# External_Power_schematic.net
KiCad netlist of a schematic drawn in Altium Designer
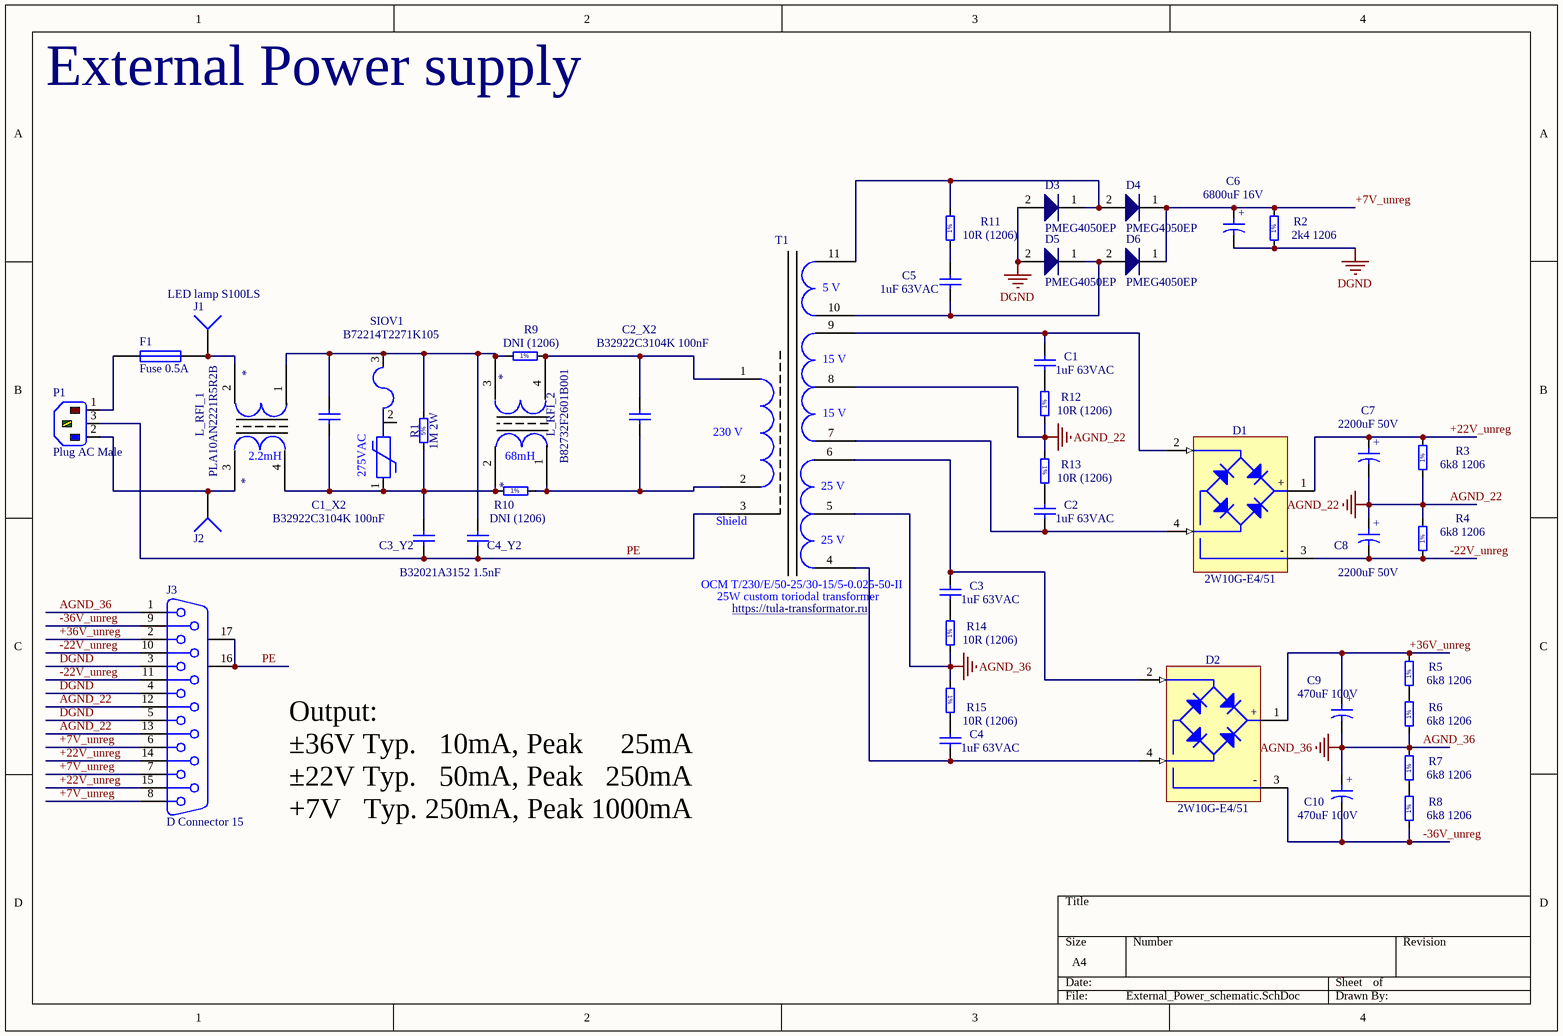
[diagram p0: External_Power_schematic.SchDoc]

(export (version "E")
  (design (tool "Eeschema 10.0.6"))
  (components
    (comp (ref "C1")
      (value "1uF 63VAC")
      (footprint "B32522C1105")
      (description "Non-polarised capacitor")
      (fields
        (field (name "PART NUMBER") "CPPR_330NF_630V_5%_2250-1050X2650X1650")
        (field (name "VOLTAGE") "630VDC/250VAC")
        (field (name "AUTHOR") "CERN DEM JLC")
      )
      (libsource (lib "Capacitors") (part "Capacitor - non polarized"))
    )
    (comp (ref "C1_X2")
      (value "B32922C3104K 100nF")
      (footprint "B32922D3334K")
      (description "Non-polarised capacitor")
      (fields
        (field (name "PART NUMBER") "CPPR_330NF_630V_5%_2250-1050X2650X1650")
        (field (name "VOLTAGE") "630VDC/250VAC")
        (field (name "AUTHOR") "CERN DEM JLC")
      )
      (libsource (lib "Capacitors") (part "Capacitor - non polarized"))
    )
    (comp (ref "C2")
      (value "1uF 63VAC")
      (footprint "B32522C1105")
      (description "Non-polarised capacitor")
      (fields
        (field (name "PART NUMBER") "CPPR_330NF_630V_5%_2250-1050X2650X1650")
        (field (name "VOLTAGE") "630VDC/250VAC")
        (field (name "AUTHOR") "CERN DEM JLC")
      )
      (libsource (lib "Capacitors") (part "Capacitor - non polarized"))
    )
    (comp (ref "C2_X2")
      (value "B32922C3104K 100nF")
      (footprint "B32922D3334K")
      (description "Non-polarised capacitor")
      (fields
        (field (name "PART NUMBER") "CPPR_330NF_630V_5%_2250-1050X2650X1650")
        (field (name "VOLTAGE") "630VDC/250VAC")
        (field (name "AUTHOR") "CERN DEM JLC")
      )
      (libsource (lib "Capacitors") (part "Capacitor - non polarized"))
    )
    (comp (ref "C3")
      (value "1uF 63VAC")
      (footprint "B32522C1105")
      (description "Non-polarised capacitor")
      (fields
        (field (name "PART NUMBER") "CPPR_330NF_630V_5%_2250-1050X2650X1650")
        (field (name "VOLTAGE") "630VDC/250VAC")
        (field (name "AUTHOR") "CERN DEM JLC")
      )
      (libsource (lib "Capacitors") (part "Capacitor - non polarized"))
    )
    (comp (ref "C3_Y2")
      (value "B32021A3152 1.5nF")
      (footprint "B32021A3152")
      (description "Non-polarised capacitor")
      (fields
        (field (name "PART NUMBER") "CPPR_330NF_630V_5%_2250-1050X2650X1650")
        (field (name "VOLTAGE") "630VDC/250VAC")
        (field (name "AUTHOR") "CERN DEM JLC")
      )
      (libsource (lib "Capacitors") (part "Capacitor - non polarized"))
    )
    (comp (ref "C4")
      (value "1uF 63VAC")
      (footprint "B32522C1105")
      (description "Non-polarised capacitor")
      (fields
        (field (name "PART NUMBER") "CPPR_330NF_630V_5%_2250-1050X2650X1650")
        (field (name "VOLTAGE") "630VDC/250VAC")
        (field (name "AUTHOR") "CERN DEM JLC")
      )
      (libsource (lib "Capacitors") (part "Capacitor - non polarized"))
    )
    (comp (ref "C4_Y2")
      (value "B32021A3152 1.5nF")
      (footprint "B32021A3152")
      (description "Non-polarised capacitor")
      (fields
        (field (name "PART NUMBER") "CPPR_330NF_630V_5%_2250-1050X2650X1650")
        (field (name "VOLTAGE") "630VDC/250VAC")
        (field (name "AUTHOR") "CERN DEM JLC")
      )
      (libsource (lib "Capacitors") (part "Capacitor - non polarized"))
    )
    (comp (ref "C5")
      (value "1uF 63VAC")
      (footprint "B32522C1475")
      (description "Non-polarised capacitor")
      (fields
        (field (name "PART NUMBER") "CPPR_330NF_630V_5%_2250-1050X2650X1650")
        (field (name "VOLTAGE") "630VDC/250VAC")
        (field (name "AUTHOR") "CERN DEM JLC")
      )
      (libsource (lib "Capacitors") (part "Capacitor - non polarized"))
    )
    (comp (ref "C6")
      (value "6800uF 16V")
      (footprint "CAPPR750-1850X3750")
      (description "Polarised capacitor")
      (fields
        (field (name "PART NUMBER") "CAER_10000UF_16V_20%_CHEMI-CON_EKYB160ELL103MMP1S")
        (field (name "VOLTAGE") "16V")
        (field (name "AUTHOR") "CERN DEM JLC")
      )
      (libsource (lib "Capacitors") (part "Capacitor - polarized"))
    )
    (comp (ref "C7")
      (value "2200uF 50V")
      (footprint "CAPPR750-1850X3750")
      (description "Polarised capacitor")
      (fields
        (field (name "PART NUMBER") "CAER_10000UF_16V_20%_CHEMI-CON_EKYB160ELL103MMP1S")
        (field (name "VOLTAGE") "16V")
        (field (name "AUTHOR") "CERN DEM JLC")
      )
      (libsource (lib "Capacitors") (part "Capacitor - polarized"))
    )
    (comp (ref "C8")
      (value "2200uF 50V")
      (footprint "CAPPR750-1850X3750")
      (description "Polarised capacitor")
      (fields
        (field (name "PART NUMBER") "CAER_10000UF_16V_20%_CHEMI-CON_EKYB160ELL103MMP1S")
        (field (name "VOLTAGE") "16V")
        (field (name "AUTHOR") "CERN DEM JLC")
      )
      (libsource (lib "Capacitors") (part "Capacitor - polarized"))
    )
    (comp (ref "C9")
      (value "470uF 100V")
      (footprint "CAPPR750-1850X3750")
      (description "Polarised capacitor")
      (fields
        (field (name "PART NUMBER") "CAER_10000UF_16V_20%_CHEMI-CON_EKYB160ELL103MMP1S")
        (field (name "VOLTAGE") "16V")
        (field (name "AUTHOR") "CERN DEM JLC")
      )
      (libsource (lib "Capacitors") (part "Capacitor - polarized"))
    )
    (comp (ref "C10")
      (value "470uF 100V")
      (footprint "CAPPR750-1850X3750")
      (description "Polarised capacitor")
      (fields
        (field (name "PART NUMBER") "CAER_10000UF_16V_20%_CHEMI-CON_EKYB160ELL103MMP1S")
        (field (name "VOLTAGE") "16V")
        (field (name "AUTHOR") "CERN DEM JLC")
      )
      (libsource (lib "Capacitors") (part "Capacitor - polarized"))
    )
    (comp (ref "D1")
      (value "2W10G-E4/51")
      (footprint "VISHAY_WOG")
      (description "Bridge Rectifier 1+ 2AC 3- 4AC")
      (fields
        (field (name "PART NUMBER") "W005G-E4/51")
        (field (name "VOLTAGE") "50V")
        (field (name "AUTHOR") "CERN DEM JLC")
      )
      (libsource (lib "ICs And Semiconductors") (part "Bridge Rectifier 1+ 2AC 3- 4AC"))
    )
    (comp (ref "D2")
      (value "2W10G-E4/51")
      (footprint "VISHAY_WOG")
      (description "Bridge Rectifier 1+ 2AC 3- 4AC")
      (fields
        (field (name "PART NUMBER") "W005G-E4/51")
        (field (name "VOLTAGE") "50V")
        (field (name "AUTHOR") "CERN DEM JLC")
      )
      (libsource (lib "ICs And Semiconductors") (part "Bridge Rectifier 1+ 2AC 3- 4AC"))
    )
    (comp (ref "D3")
      (value "PMEG4050EP")
      (footprint "PMEG4050EP")
      (libsource (lib "My SCH library") (part "PMEG4050EP"))
    )
    (comp (ref "D4")
      (value "PMEG4050EP")
      (footprint "PMEG4050EP")
      (libsource (lib "My SCH library") (part "PMEG4050EP"))
    )
    (comp (ref "D5")
      (value "PMEG4050EP")
      (footprint "PMEG4050EP")
      (libsource (lib "My SCH library") (part "PMEG4050EP"))
    )
    (comp (ref "D6")
      (value "PMEG4050EP")
      (footprint "PMEG4050EP")
      (libsource (lib "My SCH library") (part "PMEG4050EP"))
    )
    (comp (ref "F1")
      (value "Fuse 0.5A")
      (footprint "FUSE")
      (description "Fuse")
      (fields (field (name "PUBLISHER") "Altium Limited"))
      (libsource (lib "Miscellaneous Devices") (part "Fuse 1"))
    )
    (comp (ref "J1")
      (value "Socket")
      (footprint "PIN1")
      (fields (field (name "PUBLISHER") "Altium Limited"))
      (libsource (lib "Miscellaneous Connectors") (part "Socket"))
    )
    (comp (ref "J2")
      (value "Socket")
      (footprint "PIN1")
      (fields (field (name "PUBLISHER") "Altium Limited"))
      (libsource (lib "Miscellaneous Connectors") (part "Socket"))
    )
    (comp (ref "J3")
      (value "D Connector 15")
      (footprint "DSUB1.385-2H15")
      (description "Receptacle Assembly, 15 Position, Right Angle")
      (fields (field (name "PUBLISHER") "Altium Limited"))
      (libsource (lib "Miscellaneous Connectors") (part "D Connector 15"))
    )
    (comp (ref "L_RFI_1")
      (value "PLA10AN2221R5R2B")
      (footprint "PLA10AN2221R5R2B")
      (libsource (lib "") (part "PLA10AN2221R5R2B_1"))
    )
    (comp (ref "L_RFI_2")
      (value "B82732F2601B001")
      (footprint "B82732F")
      (libsource (lib "My SCH library") (part "PLA10AN2221R5R2B"))
    )
    (comp (ref "P1")
      (value "Plug AC Male")
      (footprint "AS-205")
      (description "IEC Mains Power Inlet, EN60 320-1 C14 Class I Cold Condition, PC Flange Rear Mount, Chassis Plug")
      (fields (field (name "PUBLISHER") "Altium Limited"))
      (libsource (lib "Miscellaneous Connectors") (part "Plug AC Male"))
    )
    (comp (ref "R1")
      (value "1M 2W")
      (footprint "RES_TYCO_CFR200")
      (description "Resistor - 5%")
      (fields
        (field (name "PART NUMBER") "RCF_NO-VALUE_5%_2W_0-450PPM_TYCO_CFR200")
        (field (name "POWER") "2W")
        (field (name "AUTHOR") "CERN DEM JLC")
      )
      (libsource (lib "Resistors") (part "Resistor - 5%"))
    )
    (comp (ref "R2")
      (value "2k4 1206")
      (footprint "RESC3216X65N")
      (description "Resistor - 1%")
      (fields
        (field (name "PART NUMBER") "R1206_2K4_1%_0.25W_100PPM")
        (field (name "POWER") "0.25W")
        (field (name "AUTHOR") "CERN DEM JLC")
      )
      (libsource (lib "Resistors") (part "Resistor - 1%"))
    )
    (comp (ref "R3")
      (value "6k8 1206")
      (footprint "RESC3216X65N")
      (description "Resistor - 1%")
      (fields
        (field (name "PART NUMBER") "R1206_2K4_1%_0.25W_100PPM")
        (field (name "POWER") "0.25W")
        (field (name "AUTHOR") "CERN DEM JLC")
      )
      (libsource (lib "Resistors") (part "Resistor - 1%"))
    )
    (comp (ref "R4")
      (value "6k8 1206")
      (footprint "RESC3216X65N")
      (description "Resistor - 1%")
      (fields
        (field (name "PART NUMBER") "R1206_2K4_1%_0.25W_100PPM")
        (field (name "POWER") "0.25W")
        (field (name "AUTHOR") "CERN DEM JLC")
      )
      (libsource (lib "Resistors") (part "Resistor - 1%"))
    )
    (comp (ref "R5")
      (value "6k8 1206")
      (footprint "RESC3216X65N")
      (description "Resistor - 1%")
      (fields
        (field (name "PART NUMBER") "R1206_2K4_1%_0.25W_100PPM")
        (field (name "POWER") "0.25W")
        (field (name "AUTHOR") "CERN DEM JLC")
      )
      (libsource (lib "Resistors") (part "Resistor - 1%"))
    )
    (comp (ref "R6")
      (value "6k8 1206")
      (footprint "RESC3216X65N")
      (description "Resistor - 1%")
      (fields
        (field (name "PART NUMBER") "R1206_2K4_1%_0.25W_100PPM")
        (field (name "POWER") "0.25W")
        (field (name "AUTHOR") "CERN DEM JLC")
      )
      (libsource (lib "Resistors") (part "Resistor - 1%"))
    )
    (comp (ref "R7")
      (value "6k8 1206")
      (footprint "RESC3216X65N")
      (description "Resistor - 1%")
      (fields
        (field (name "PART NUMBER") "R1206_2K4_1%_0.25W_100PPM")
        (field (name "POWER") "0.25W")
        (field (name "AUTHOR") "CERN DEM JLC")
      )
      (libsource (lib "Resistors") (part "Resistor - 1%"))
    )
    (comp (ref "R8")
      (value "6k8 1206")
      (footprint "RESC3216X65N")
      (description "Resistor - 1%")
      (fields
        (field (name "PART NUMBER") "R1206_2K4_1%_0.25W_100PPM")
        (field (name "POWER") "0.25W")
        (field (name "AUTHOR") "CERN DEM JLC")
      )
      (libsource (lib "Resistors") (part "Resistor - 1%"))
    )
    (comp (ref "R9")
      (value "DNI (1206)")
      (footprint "RESC3216X65N")
      (description "Resistor - 1%")
      (fields
        (field (name "PART NUMBER") "R1206_2K4_1%_0.25W_100PPM")
        (field (name "POWER") "0.25W")
        (field (name "AUTHOR") "CERN DEM JLC")
      )
      (libsource (lib "Resistors") (part "Resistor - 1%"))
    )
    (comp (ref "R10")
      (value "DNI (1206)")
      (footprint "RESC3216X65N")
      (description "Resistor - 1%")
      (fields
        (field (name "PART NUMBER") "R1206_2K4_1%_0.25W_100PPM")
        (field (name "POWER") "0.25W")
        (field (name "AUTHOR") "CERN DEM JLC")
      )
      (libsource (lib "Resistors") (part "Resistor - 1%"))
    )
    (comp (ref "R11")
      (value "10R (1206)")
      (footprint "RESC3216X65N")
      (description "Resistor - 1%")
      (fields
        (field (name "PART NUMBER") "R1206_2K4_1%_0.25W_100PPM")
        (field (name "POWER") "0.25W")
        (field (name "AUTHOR") "CERN DEM JLC")
      )
      (libsource (lib "Resistors") (part "Resistor - 1%"))
    )
    (comp (ref "R12")
      (value "10R (1206)")
      (footprint "RESC3216X65N")
      (description "Resistor - 1%")
      (fields
        (field (name "PART NUMBER") "R1206_2K4_1%_0.25W_100PPM")
        (field (name "POWER") "0.25W")
        (field (name "AUTHOR") "CERN DEM JLC")
      )
      (libsource (lib "Resistors") (part "Resistor - 1%"))
    )
    (comp (ref "R13")
      (value "10R (1206)")
      (footprint "RESC3216X65N")
      (description "Resistor - 1%")
      (fields
        (field (name "PART NUMBER") "R1206_2K4_1%_0.25W_100PPM")
        (field (name "POWER") "0.25W")
        (field (name "AUTHOR") "CERN DEM JLC")
      )
      (libsource (lib "Resistors") (part "Resistor - 1%"))
    )
    (comp (ref "R14")
      (value "10R (1206)")
      (footprint "RESC3216X65N")
      (description "Resistor - 1%")
      (fields
        (field (name "PART NUMBER") "R1206_2K4_1%_0.25W_100PPM")
        (field (name "POWER") "0.25W")
        (field (name "AUTHOR") "CERN DEM JLC")
      )
      (libsource (lib "Resistors") (part "Resistor - 1%"))
    )
    (comp (ref "R15")
      (value "10R (1206)")
      (footprint "RESC3216X65N")
      (description "Resistor - 1%")
      (fields
        (field (name "PART NUMBER") "R1206_2K4_1%_0.25W_100PPM")
        (field (name "POWER") "0.25W")
        (field (name "AUTHOR") "CERN DEM JLC")
      )
      (libsource (lib "Resistors") (part "Resistor - 1%"))
    )
    (comp (ref "SIOV1")
      (value "B72214T2271K105")
      (footprint "B72214T2271K105")
      (fields (field (name "ORDER") "B72214T2271K105") (field (name "PUBLISHER") "Altium Limited"))
      (libsource (lib "My SCH library") (part "B72214T2271K105"))
    )
    (comp (ref "T1")
      (value "OCM T/230/E/50-25/30-15/5-0.025-50-II")
      (footprint "OCM T/230/E/50-25/30-15/5-0.025-50-II")
      (libsource (lib "My SCH library") (part "OCM T/230/E/50-25/30-15/5-0.025-50-II"))
    )
  )
  (nets
    (net (code "1") (name "/+7V_unreg") (class "Default")
      (node (ref "C6") (pin "1") (pinfunction "1_1") (pintype "passive"))
      (node (ref "D4") (pin "1") (pinfunction "1_1") (pintype "passive"))
      (node (ref "D6") (pin "1") (pinfunction "1_1") (pintype "passive"))
      (node (ref "J3") (pin "6") (pinfunction "6_6") (pintype "passive"))
      (node (ref "J3") (pin "7") (pinfunction "7_7") (pintype "passive"))
      (node (ref "J3") (pin "8") (pinfunction "8_8") (pintype "passive"))
      (node (ref "R2") (pin "2") (pinfunction "2_2") (pintype "passive"))
    )
    (net (code "2") (name "/+22V_unreg") (class "Default")
      (node (ref "C7") (pin "1") (pinfunction "1_1") (pintype "passive"))
      (node (ref "D1") (pin "1") (pinfunction "+_1") (pintype "power_in"))
      (node (ref "J3") (pin "14") (pinfunction "14_14") (pintype "passive"))
      (node (ref "J3") (pin "15") (pinfunction "15_15") (pintype "passive"))
      (node (ref "R3") (pin "2") (pinfunction "2_2") (pintype "passive"))
    )
    (net (code "3") (name "/+36V_unreg") (class "Default")
      (node (ref "C9") (pin "1") (pinfunction "1_1") (pintype "passive"))
      (node (ref "D2") (pin "1") (pinfunction "+_1") (pintype "power_in"))
      (node (ref "J3") (pin "2") (pinfunction "2_2") (pintype "passive"))
      (node (ref "R5") (pin "2") (pinfunction "2_2") (pintype "passive"))
    )
    (net (code "4") (name "/-22V_unreg") (class "Default")
      (node (ref "C8") (pin "2") (pinfunction "2_2") (pintype "passive"))
      (node (ref "D1") (pin "3") (pinfunction "-_3") (pintype "power_in"))
      (node (ref "J3") (pin "10") (pinfunction "10_10") (pintype "passive"))
      (node (ref "J3") (pin "11") (pinfunction "11_11") (pintype "passive"))
      (node (ref "R4") (pin "1") (pinfunction "1_1") (pintype "passive"))
    )
    (net (code "5") (name "/-36V_unreg") (class "Default")
      (node (ref "C10") (pin "2") (pinfunction "2_2") (pintype "passive"))
      (node (ref "D2") (pin "3") (pinfunction "-_3") (pintype "power_in"))
      (node (ref "J3") (pin "9") (pinfunction "9_9") (pintype "passive"))
      (node (ref "R8") (pin "1") (pinfunction "1_1") (pintype "passive"))
    )
    (net (code "6") (name "/PE") (class "Default")
      (node (ref "C3_Y2") (pin "1") (pinfunction "1_1") (pintype "passive"))
      (node (ref "C4_Y2") (pin "1") (pinfunction "1_1") (pintype "passive"))
      (node (ref "J3") (pin "16") (pinfunction "MH1_16") (pintype "passive"))
      (node (ref "J3") (pin "17") (pinfunction "MH2_17") (pintype "passive"))
      (node (ref "P1") (pin "3") (pinfunction "E_3") (pintype "power_in"))
      (node (ref "T1") (pin "3") (pinfunction "3_3") (pintype "passive"))
    )
    (net (code "7") (name "AGND_22") (class "Default")
      (node (ref "C7") (pin "2") (pinfunction "2_2") (pintype "passive"))
      (node (ref "C8") (pin "1") (pinfunction "1_1") (pintype "passive"))
      (node (ref "J3") (pin "12") (pinfunction "12_12") (pintype "passive"))
      (node (ref "J3") (pin "13") (pinfunction "13_13") (pintype "passive"))
      (node (ref "R12") (pin "1") (pinfunction "1_1") (pintype "passive"))
      (node (ref "R13") (pin "1") (pinfunction "1_1") (pintype "passive"))
      (node (ref "R3") (pin "1") (pinfunction "1_1") (pintype "passive"))
      (node (ref "R4") (pin "2") (pinfunction "2_2") (pintype "passive"))
      (node (ref "T1") (pin "8") (pinfunction "8_8") (pintype "passive"))
    )
    (net (code "8") (name "AGND_36") (class "Default")
      (node (ref "C10") (pin "1") (pinfunction "1_1") (pintype "passive"))
      (node (ref "C9") (pin "2") (pinfunction "2_2") (pintype "passive"))
      (node (ref "J3") (pin "1") (pinfunction "1_1") (pintype "passive"))
      (node (ref "R14") (pin "1") (pinfunction "1_1") (pintype "passive"))
      (node (ref "R15") (pin "1") (pinfunction "1_1") (pintype "passive"))
      (node (ref "R6") (pin "1") (pinfunction "1_1") (pintype "passive"))
      (node (ref "R7") (pin "2") (pinfunction "2_2") (pintype "passive"))
      (node (ref "T1") (pin "5") (pinfunction "5_5") (pintype "passive"))
    )
    (net (code "9") (name "DGND") (class "Default")
      (node (ref "C6") (pin "2") (pinfunction "2_2") (pintype "passive"))
      (node (ref "D3") (pin "2") (pinfunction "2_2") (pintype "passive"))
      (node (ref "D5") (pin "2") (pinfunction "2_2") (pintype "passive"))
      (node (ref "J3") (pin "3") (pinfunction "3_3") (pintype "passive"))
      (node (ref "J3") (pin "4") (pinfunction "4_4") (pintype "passive"))
      (node (ref "J3") (pin "5") (pinfunction "5_5") (pintype "passive"))
      (node (ref "R2") (pin "1") (pinfunction "1_1") (pintype "passive"))
    )
    (net (code "10") (name "Net-(C1-Pad1)") (class "Default")
      (node (ref "C1") (pin "1") (pinfunction "1_1") (pintype "passive"))
      (node (ref "R12") (pin "2") (pinfunction "2_2") (pintype "passive"))
    )
    (net (code "11") (name "Net-(C1-Pad2)") (class "Default")
      (node (ref "C1") (pin "2") (pinfunction "2_2") (pintype "passive"))
      (node (ref "D1") (pin "2") (pinfunction "AC_2") (pintype "input"))
      (node (ref "T1") (pin "9") (pinfunction "9_9") (pintype "passive"))
    )
    (net (code "12") (name "Net-(C1_X2-Pad1)") (class "Default")
      (node (ref "C1_X2") (pin "1") (pinfunction "1_1") (pintype "passive"))
      (node (ref "C3_Y2") (pin "2") (pinfunction "2_2") (pintype "passive"))
      (node (ref "L_RFI_1") (pin "4") (pinfunction "4_4") (pintype "passive"))
      (node (ref "L_RFI_2") (pin "2") (pinfunction "2_2") (pintype "passive"))
      (node (ref "R1") (pin "1") (pinfunction "1_1") (pintype "passive"))
      (node (ref "R10") (pin "1") (pinfunction "1_1") (pintype "passive"))
      (node (ref "SIOV1") (pin "1") (pinfunction "1_1") (pintype "passive"))
    )
    (net (code "13") (name "Net-(C1_X2-Pad2)") (class "Default")
      (node (ref "C1_X2") (pin "2") (pinfunction "2_2") (pintype "passive"))
      (node (ref "C4_Y2") (pin "2") (pinfunction "2_2") (pintype "passive"))
      (node (ref "L_RFI_1") (pin "1") (pinfunction "1_1") (pintype "passive"))
      (node (ref "L_RFI_2") (pin "3") (pinfunction "3_3") (pintype "passive"))
      (node (ref "R1") (pin "2") (pinfunction "2_2") (pintype "passive"))
      (node (ref "R9") (pin "1") (pinfunction "1_1") (pintype "passive"))
      (node (ref "SIOV1") (pin "3") (pinfunction "3_3") (pintype "passive"))
    )
    (net (code "14") (name "Net-(C2-Pad1)") (class "Default")
      (node (ref "C2") (pin "1") (pinfunction "1_1") (pintype "passive"))
      (node (ref "D1") (pin "4") (pinfunction "AC_4") (pintype "input"))
      (node (ref "T1") (pin "7") (pinfunction "8_7") (pintype "passive"))
    )
    (net (code "15") (name "Net-(C2-Pad2)") (class "Default")
      (node (ref "C2") (pin "2") (pinfunction "2_2") (pintype "passive"))
      (node (ref "R13") (pin "2") (pinfunction "2_2") (pintype "passive"))
    )
    (net (code "16") (name "Net-(C2_X2-Pad1)") (class "Default")
      (node (ref "C2_X2") (pin "1") (pinfunction "1_1") (pintype "passive"))
      (node (ref "L_RFI_2") (pin "1") (pinfunction "1_1") (pintype "passive"))
      (node (ref "R10") (pin "2") (pinfunction "2_2") (pintype "passive"))
      (node (ref "T1") (pin "2") (pintype "passive"))
    )
    (net (code "17") (name "Net-(C2_X2-Pad2)") (class "Default")
      (node (ref "C2_X2") (pin "2") (pinfunction "2_2") (pintype "passive"))
      (node (ref "L_RFI_2") (pin "4") (pinfunction "4_4") (pintype "passive"))
      (node (ref "R9") (pin "2") (pinfunction "2_2") (pintype "passive"))
      (node (ref "T1") (pin "1") (pinfunction "1_1") (pintype "passive"))
    )
    (net (code "18") (name "Net-(C3-Pad1)") (class "Default")
      (node (ref "C3") (pin "1") (pinfunction "1_1") (pintype "passive"))
      (node (ref "R14") (pin "2") (pinfunction "2_2") (pintype "passive"))
    )
    (net (code "19") (name "Net-(C3-Pad2)") (class "Default")
      (node (ref "C3") (pin "2") (pinfunction "2_2") (pintype "passive"))
      (node (ref "D2") (pin "2") (pinfunction "AC_2") (pintype "input"))
      (node (ref "T1") (pin "6") (pinfunction "6_6") (pintype "passive"))
    )
    (net (code "20") (name "Net-(C4-Pad1)") (class "Default")
      (node (ref "C4") (pin "1") (pinfunction "1_1") (pintype "passive"))
      (node (ref "D2") (pin "4") (pinfunction "AC_4") (pintype "input"))
      (node (ref "T1") (pin "4") (pinfunction "4_4") (pintype "passive"))
    )
    (net (code "21") (name "Net-(C4-Pad2)") (class "Default")
      (node (ref "C4") (pin "2") (pinfunction "2_2") (pintype "passive"))
      (node (ref "R15") (pin "2") (pinfunction "2_2") (pintype "passive"))
    )
    (net (code "22") (name "Net-(C5-Pad1)") (class "Default")
      (node (ref "C5") (pin "1") (pinfunction "1_1") (pintype "passive"))
      (node (ref "D5") (pin "1") (pinfunction "1_1") (pintype "passive"))
      (node (ref "D6") (pin "2") (pinfunction "2_2") (pintype "passive"))
      (node (ref "T1") (pin "10") (pinfunction "5_10") (pintype "passive"))
    )
    (net (code "23") (name "Net-(C5-Pad2)") (class "Default")
      (node (ref "C5") (pin "2") (pinfunction "2_2") (pintype "passive"))
      (node (ref "R11") (pin "1") (pinfunction "1_1") (pintype "passive"))
    )
    (net (code "24") (name "Net-(D3-Pad1)") (class "Default")
      (node (ref "D3") (pin "1") (pinfunction "1_1") (pintype "passive"))
      (node (ref "D4") (pin "2") (pinfunction "2_2") (pintype "passive"))
      (node (ref "R11") (pin "2") (pinfunction "2_2") (pintype "passive"))
      (node (ref "T1") (pin "11") (pinfunction "11_11") (pintype "passive"))
    )
    (net (code "25") (name "Net-(F1-Pad2)") (class "Default")
      (node (ref "F1") (pin "2") (pinfunction "2_2") (pintype "passive"))
      (node (ref "J1") (pin "1") (pinfunction "1_1") (pintype "passive"))
      (node (ref "L_RFI_1") (pin "2") (pinfunction "2_2") (pintype "passive"))
    )
    (net (code "26") (name "Net-(P1-L)") (class "Default")
      (node (ref "F1") (pin "1") (pinfunction "1_1") (pintype "passive"))
      (node (ref "P1") (pin "1") (pinfunction "L_1") (pintype "power_in"))
    )
    (net (code "27") (name "Net-(P1-N)") (class "Default")
      (node (ref "J2") (pin "1") (pinfunction "1_1") (pintype "passive"))
      (node (ref "L_RFI_1") (pin "3") (pinfunction "3_3") (pintype "passive"))
      (node (ref "P1") (pin "2") (pinfunction "N_2") (pintype "power_in"))
    )
    (net (code "28") (name "Net-(R5-Pad1)") (class "Default")
      (node (ref "R5") (pin "1") (pinfunction "1_1") (pintype "passive"))
      (node (ref "R6") (pin "2") (pinfunction "2_2") (pintype "passive"))
    )
    (net (code "29") (name "Net-(R7-Pad1)") (class "Default")
      (node (ref "R7") (pin "1") (pinfunction "1_1") (pintype "passive"))
      (node (ref "R8") (pin "2") (pinfunction "2_2") (pintype "passive"))
    )
    (net (code "30") (name "unconnected-(SIOV1-Pad2)") (class "Default")
      (node (ref "SIOV1") (pin "2") (pinfunction "2_2") (pintype "passive"))
    )
  )
)
